# i6_Dimmer.net
KiCad netlist of a schematic drawn in EAGLE
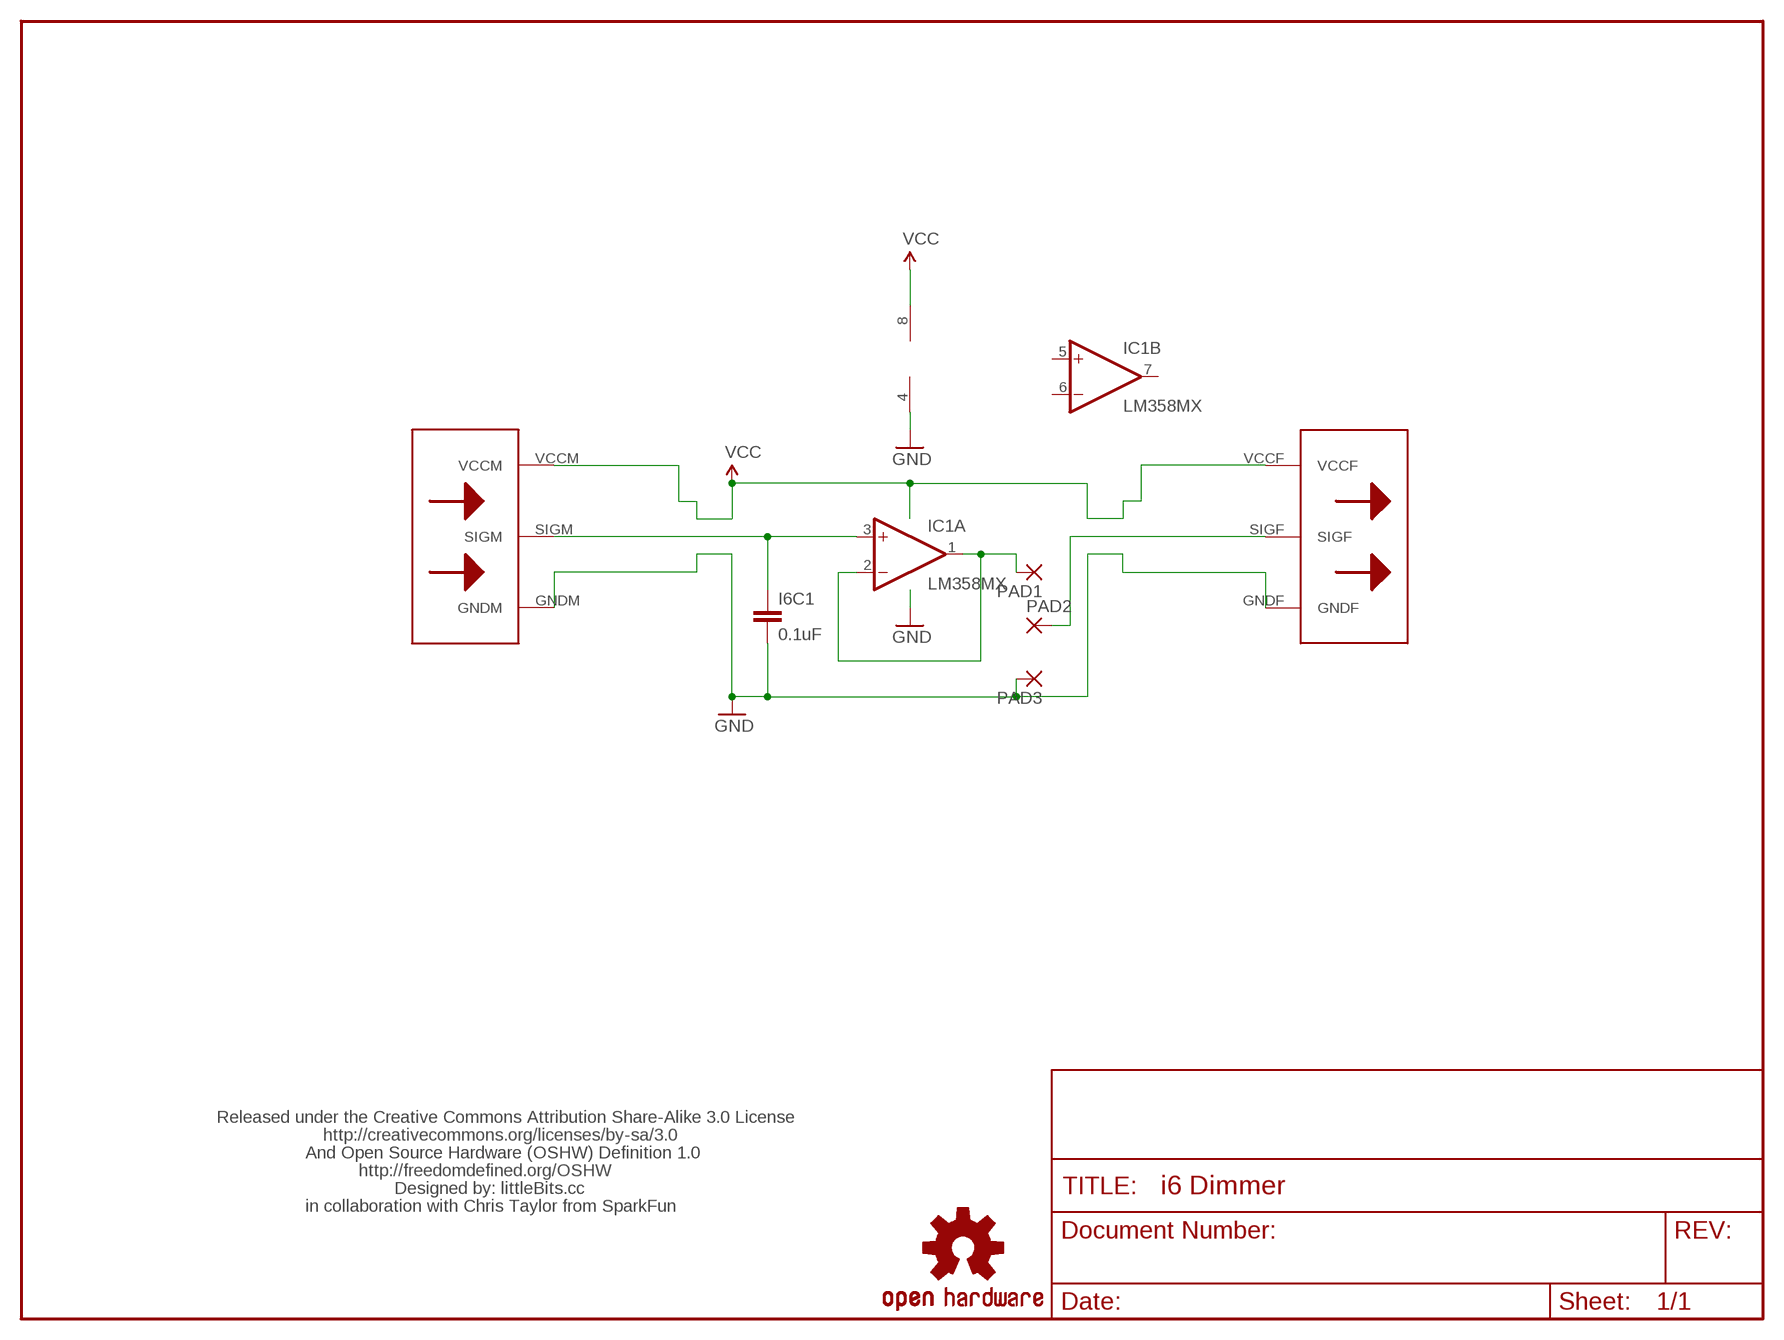
[diagram p0: schematic, sheet 1]

(export (version "E")
  (design (tool "Eeschema 10.0.6"))
  (components
    (comp (ref "I6C1")
      (value "0.1uF")
      (footprint "eagle-import:1206")
      (libsource (lib "eagle-import") (part "CAP1206"))
    )
    (comp (ref "IC1")
      (value "LM358MX")
      (footprint "eagle-import:SO08")
      (libsource (lib "eagle-import") (part "LM358MX"))
    )
    (comp (ref "PAD1")
      (value "SMD5")
      (footprint "eagle-import:SMD2,54-5,08")
      (libsource (lib "eagle-import") (part "SMD5"))
    )
    (comp (ref "PAD2")
      (value "SMD5")
      (footprint "eagle-import:SMD2,54-5,08")
      (libsource (lib "eagle-import") (part "SMD5"))
    )
    (comp (ref "PAD3")
      (value "SMD5")
      (footprint "eagle-import:SMD2,54-5,08")
      (libsource (lib "eagle-import") (part "SMD5"))
    )
    (comp (ref "U$1")
      (value "LB_CREDITS")
      (footprint "eagle-import:OSHWCREDIT")
      (libsource (lib "eagle-import") (part "LB_CREDITS"))
    )
    (comp (ref "U$3")
      (value "OSHW-LOGOL")
      (footprint "eagle-import:OSHW-LOGO-L")
      (libsource (lib "eagle-import") (part "OSHW-LOGOL"))
    )
    (comp (ref "U$6")
      (value "BIGBIT")
      (footprint "eagle-import:BIGBIT")
      (libsource (lib "eagle-import") (part "BIGBIT"))
    )
  )
  (nets
    (net (code "1") (name "GND") (class "Default")
      (node (ref "I6C1") (pin "2") (pinfunction "2_2") (pintype "passive"))
      (node (ref "IC1") (pin "4") (pinfunction "V-_4") (pintype "power_in"))
      (node (ref "PAD3") (pin "1") (pinfunction "P_1") (pintype "passive"))
      (node (ref "U$6") (pin "GNDF") (pinfunction "GNDF_GNDF") (pintype "bidirectional"))
      (node (ref "U$6") (pin "GNDM") (pinfunction "GNDM_GNDM") (pintype "bidirectional"))
    )
    (net (code "2") (name "Net-(IC1A-+IN)") (class "Default")
      (node (ref "I6C1") (pin "1") (pinfunction "1_1") (pintype "passive"))
      (node (ref "IC1") (pin "3") (pinfunction "+IN_3") (pintype "input"))
      (node (ref "U$6") (pin "SIGM") (pinfunction "SIGM_SIGM") (pintype "bidirectional"))
    )
    (net (code "3") (name "Net-(IC1A--IN)") (class "Default")
      (node (ref "IC1") (pin "1") (pinfunction "OUT_1") (pintype "output"))
      (node (ref "IC1") (pin "2") (pinfunction "-IN_2") (pintype "input"))
      (node (ref "PAD1") (pin "1") (pinfunction "P_1") (pintype "passive"))
    )
    (net (code "4") (name "Net-(PAD2-P)") (class "Default")
      (node (ref "PAD2") (pin "1") (pinfunction "P_1") (pintype "passive"))
      (node (ref "U$6") (pin "SIGF") (pinfunction "SIGF_SIGF") (pintype "bidirectional"))
    )
    (net (code "5") (name "VCC") (class "Default")
      (node (ref "IC1") (pin "8") (pinfunction "V+_8") (pintype "power_in"))
      (node (ref "U$6") (pin "VCCF") (pinfunction "VCCF_VCCF") (pintype "bidirectional"))
      (node (ref "U$6") (pin "VCCM") (pinfunction "VCCM_VCCM") (pintype "bidirectional"))
    )
    (net (code "6") (name "unconnected-(IC1B-+IN-Pad5)") (class "Default")
      (node (ref "IC1") (pin "5") (pinfunction "+IN_5") (pintype "input"))
    )
    (net (code "7") (name "unconnected-(IC1B--IN-Pad6)") (class "Default")
      (node (ref "IC1") (pin "6") (pinfunction "-IN_6") (pintype "input"))
    )
    (net (code "8") (name "unconnected-(IC1B-OUT-Pad7)") (class "Default")
      (node (ref "IC1") (pin "7") (pinfunction "OUT_7") (pintype "output"))
    )
  )
)
